# 3_0V_regulator.net
KiCad netlist of a schematic drawn in Altium Designer
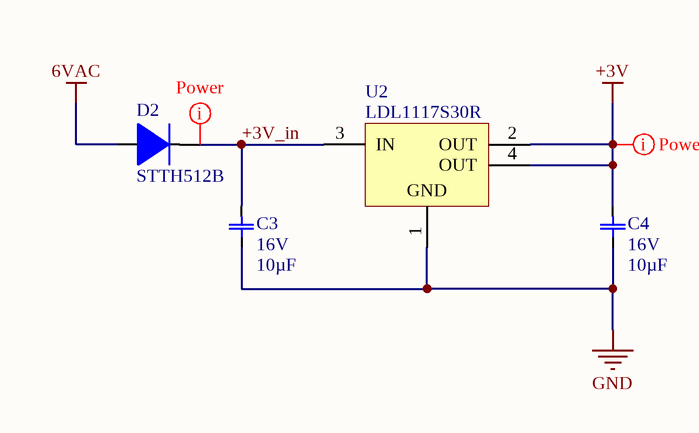
[diagram p0: 3.0V_regulator.SchDoc]

(export (version "E")
  (design (tool "Eeschema 10.0.6"))
  (components
    (comp (ref "C3")
      (value "10µF")
      (footprint "MLCC_1210")
      (description "MLCC 10µF 16V 1210")
      (fields (field (name "VOLTAGE") "16V"))
      (libsource (lib "Nixie") (part "MLCC 10µF 16V 1210"))
    )
    (comp (ref "C4")
      (value "10µF")
      (footprint "MLCC_1210")
      (description "MLCC 10µF 16V 1210")
      (fields (field (name "VOLTAGE") "16V"))
      (libsource (lib "Nixie") (part "MLCC 10µF 16V 1210"))
    )
    (comp (ref "D2")
      (value "STTH512B")
      (footprint "STTH512B")
      (description "Ultrafast recovery - 1200 V diode")
      (libsource (lib "Nixie") (part "STTH512B"))
    )
    (comp (ref "U2")
      (value "LDL1117S30R")
      (footprint "TLV1117")
      (description "Fixed LDO Voltage Regulator, 2.6 V to 18 V input, 75 mV Dropout, 3 V / 1.2 A out, SOT-223-4")
      (fields (field (name "PARTNUMBER") "TLV1117LV12DCYT") (field (name "MANUFACTURER") "Texas Instruments"))
      (libsource (lib "Nixie") (part "LDL1117S30R"))
    )
  )
  (nets
    (net (code "1") (name "+3V") (class "Default")
      (node (ref "C4") (pin "2") (pinfunction "2_2") (pintype "passive"))
      (node (ref "U2") (pin "2") (pinfunction "OUT_2") (pintype "power_in"))
      (node (ref "U2") (pin "4") (pinfunction "OUT_4") (pintype "power_in"))
    )
    (net (code "2") (name "/+3V_in") (class "Default")
      (node (ref "C3") (pin "2") (pinfunction "2_2") (pintype "passive"))
      (node (ref "D2") (pin "K") (pinfunction "K_K") (pintype "passive"))
      (node (ref "U2") (pin "3") (pinfunction "IN_3") (pintype "power_in"))
    )
    (net (code "3") (name "6VAC") (class "Default")
      (node (ref "D2") (pin "A") (pinfunction "A_A") (pintype "passive"))
    )
    (net (code "4") (name "GND") (class "Default")
      (node (ref "C3") (pin "1") (pinfunction "1_1") (pintype "passive"))
      (node (ref "C4") (pin "1") (pinfunction "1_1") (pintype "passive"))
      (node (ref "U2") (pin "1") (pinfunction "GND_1") (pintype "power_in"))
    )
  )
)
